# TEC_DRV.net
KiCad netlist of a schematic drawn in Altium Designer
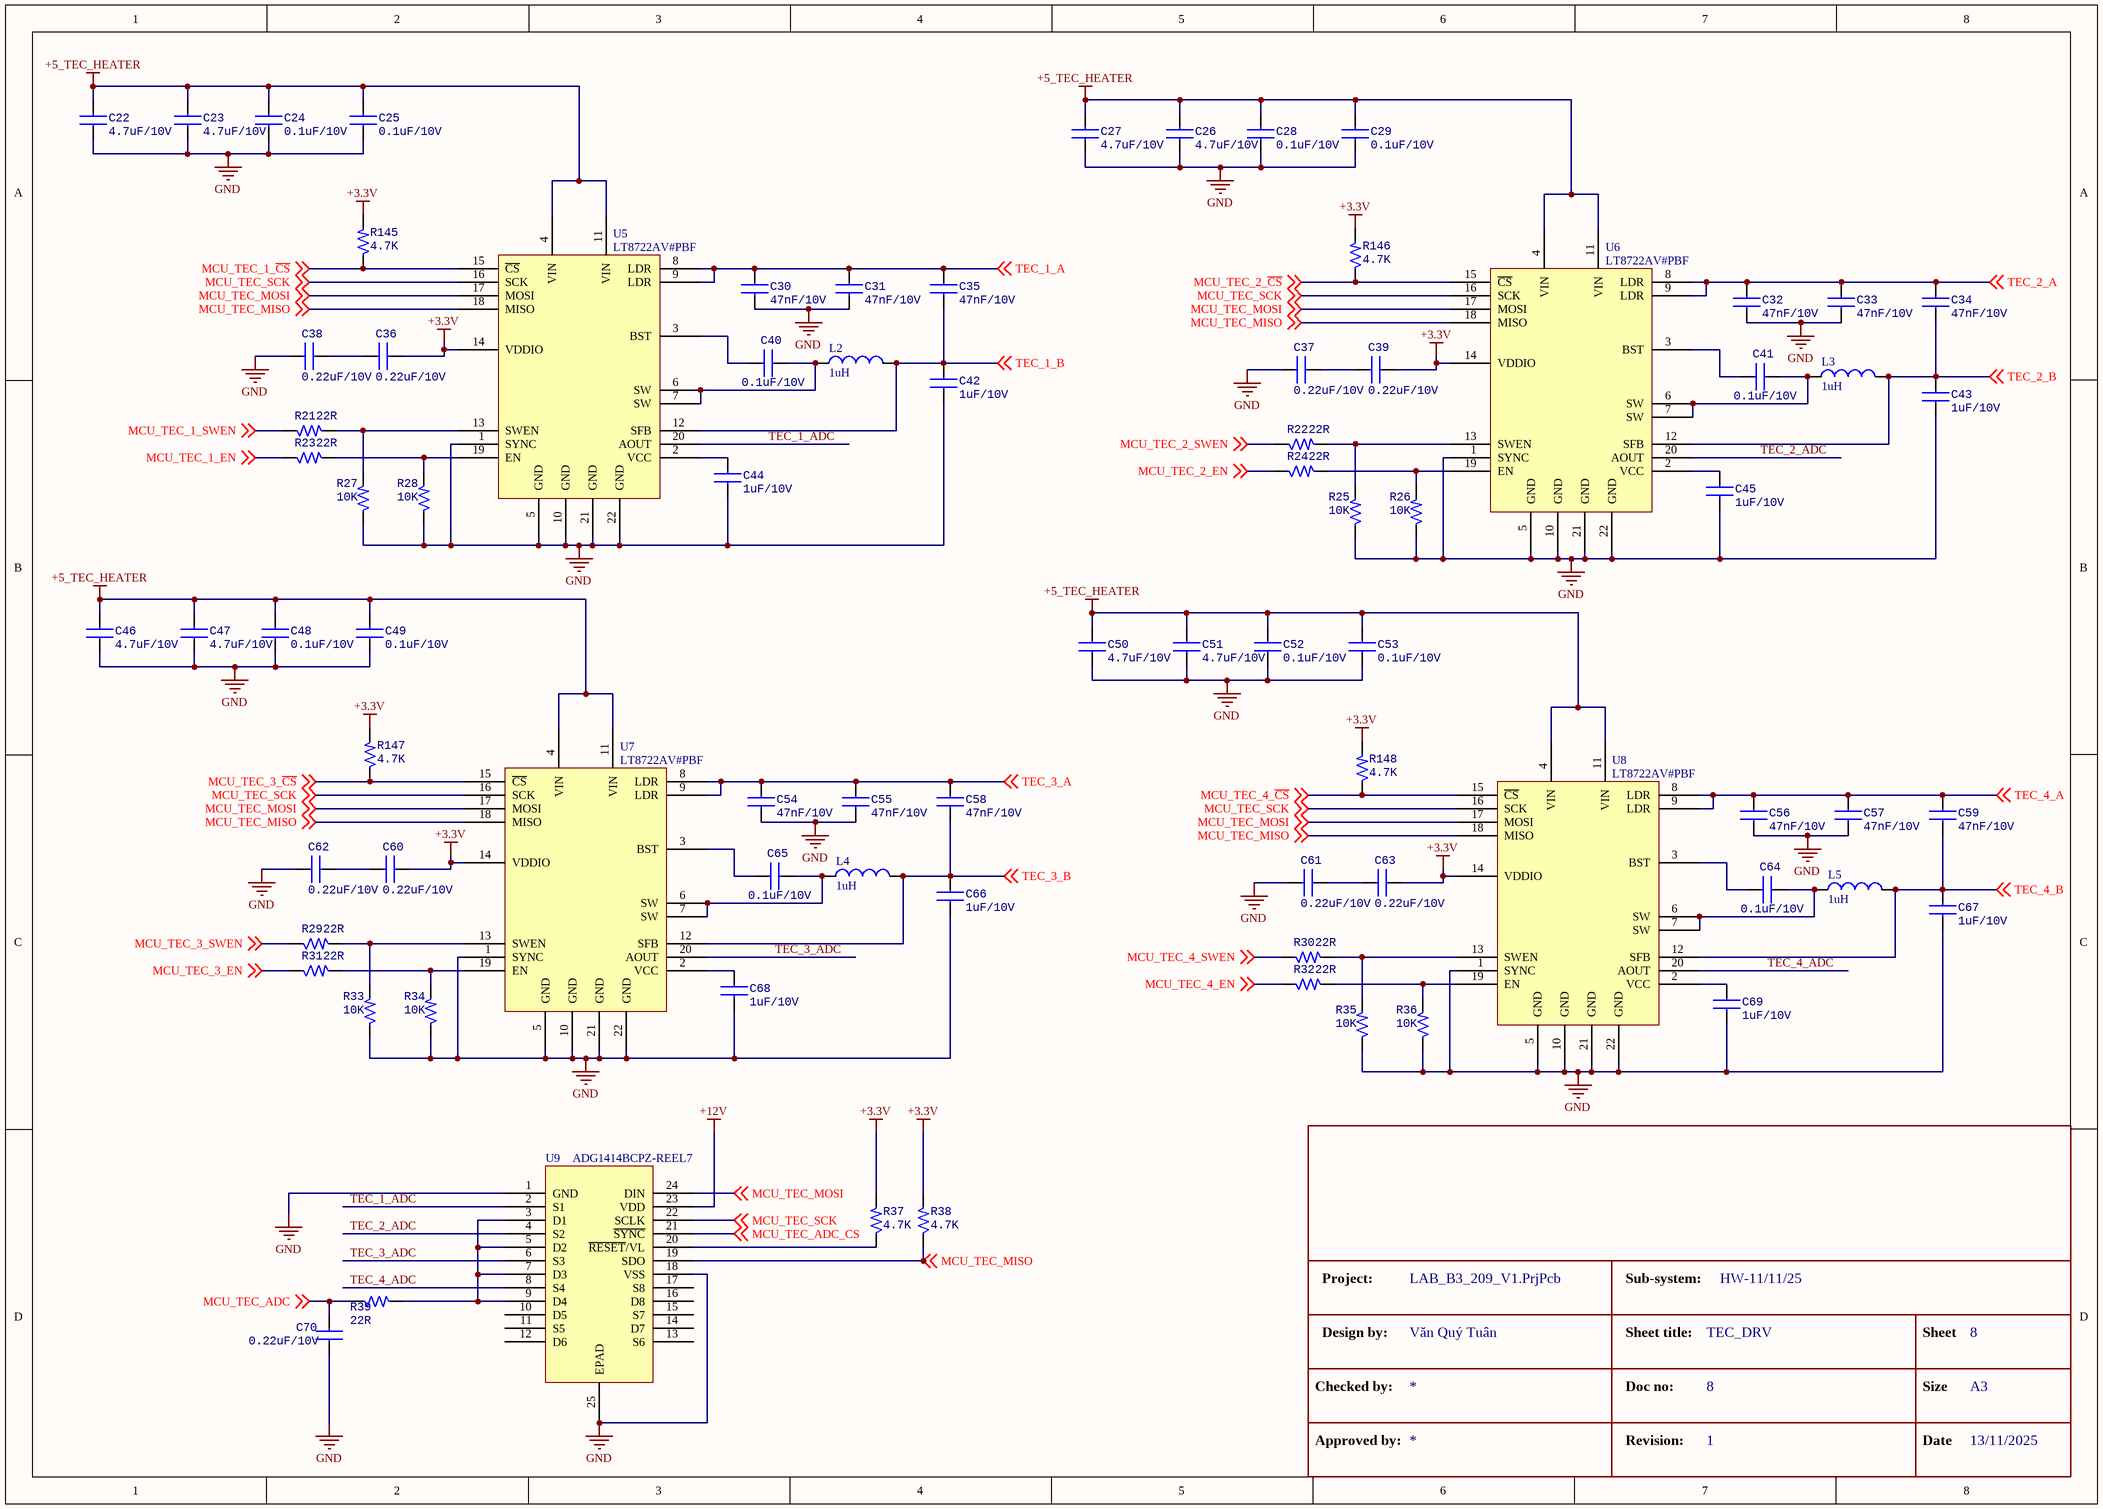
[diagram p0: TEC_DRV.SchDoc]

(export (version "E")
  (design (tool "Eeschema 10.0.6"))
  (components
    (comp (ref "C22") (value "4.7uF/10V") (footprint "CAP-CER-0603") (libsource (lib "ID") (part "CAP-CER")))
    (comp (ref "C23") (value "4.7uF/10V") (footprint "CAP-CER-0603") (libsource (lib "ID") (part "CAP-CER")))
    (comp (ref "C24") (value "0.1uF/10V") (footprint "CAP-CER-0603") (libsource (lib "ID") (part "CAP-CER")))
    (comp (ref "C25") (value "0.1uF/10V") (footprint "CAP-CER-0603") (libsource (lib "ID") (part "CAP-CER")))
    (comp (ref "C26") (value "4.7uF/10V") (footprint "CAP-CER-0603") (libsource (lib "ID") (part "CAP-CER")))
    (comp (ref "C27") (value "4.7uF/10V") (footprint "CAP-CER-0603") (libsource (lib "ID") (part "CAP-CER")))
    (comp (ref "C28") (value "0.1uF/10V") (footprint "CAP-CER-0603") (libsource (lib "ID") (part "CAP-CER")))
    (comp (ref "C29") (value "0.1uF/10V") (footprint "CAP-CER-0603") (libsource (lib "ID") (part "CAP-CER")))
    (comp (ref "C30") (value "47nF/10V") (footprint "CAP-CER-0603") (libsource (lib "ID") (part "CAP-CER")))
    (comp (ref "C31") (value "47nF/10V") (footprint "CAP-CER-0603") (libsource (lib "ID") (part "CAP-CER")))
    (comp (ref "C32") (value "47nF/10V") (footprint "CAP-CER-0603") (libsource (lib "ID") (part "CAP-CER")))
    (comp (ref "C33") (value "47nF/10V") (footprint "CAP-CER-0603") (libsource (lib "ID") (part "CAP-CER")))
    (comp (ref "C34") (value "47nF/10V") (footprint "CAP-CER-0603") (libsource (lib "ID") (part "CAP-CER")))
    (comp (ref "C35") (value "47nF/10V") (footprint "CAP-CER-0603") (libsource (lib "ID") (part "CAP-CER")))
    (comp (ref "C36") (value "0.22uF/10V") (footprint "CAP-CER-0603") (libsource (lib "ID") (part "CAP-CER")))
    (comp (ref "C37") (value "0.22uF/10V") (footprint "CAP-CER-0603") (libsource (lib "ID") (part "CAP-CER")))
    (comp (ref "C38") (value "0.22uF/10V") (footprint "CAP-CER-0603") (libsource (lib "ID") (part "CAP-CER")))
    (comp (ref "C39") (value "0.22uF/10V") (footprint "CAP-CER-0603") (libsource (lib "ID") (part "CAP-CER")))
    (comp (ref "C40") (value "0.1uF/10V") (footprint "CAP-CER-0603") (libsource (lib "ID") (part "CAP-CER")))
    (comp (ref "C41") (value "0.1uF/10V") (footprint "CAP-CER-0603") (libsource (lib "ID") (part "CAP-CER")))
    (comp (ref "C42") (value "1uF/10V") (footprint "CAP-CER-0603") (libsource (lib "ID") (part "CAP-CER")))
    (comp (ref "C43") (value "1uF/10V") (footprint "CAP-CER-0603") (libsource (lib "ID") (part "CAP-CER")))
    (comp (ref "C44") (value "1uF/10V") (footprint "CAP-CER-0603") (libsource (lib "ID") (part "CAP-CER")))
    (comp (ref "C45") (value "1uF/10V") (footprint "CAP-CER-0603") (libsource (lib "ID") (part "CAP-CER")))
    (comp (ref "C46") (value "4.7uF/10V") (footprint "CAP-CER-0603") (libsource (lib "ID") (part "CAP-CER")))
    (comp (ref "C47") (value "4.7uF/10V") (footprint "CAP-CER-0603") (libsource (lib "ID") (part "CAP-CER")))
    (comp (ref "C48") (value "0.1uF/10V") (footprint "CAP-CER-0603") (libsource (lib "ID") (part "CAP-CER")))
    (comp (ref "C49") (value "0.1uF/10V") (footprint "CAP-CER-0603") (libsource (lib "ID") (part "CAP-CER")))
    (comp (ref "C50") (value "4.7uF/10V") (footprint "CAP-CER-0603") (libsource (lib "ID") (part "CAP-CER")))
    (comp (ref "C51") (value "4.7uF/10V") (footprint "CAP-CER-0603") (libsource (lib "ID") (part "CAP-CER")))
    (comp (ref "C52") (value "0.1uF/10V") (footprint "CAP-CER-0603") (libsource (lib "ID") (part "CAP-CER")))
    (comp (ref "C53") (value "0.1uF/10V") (footprint "CAP-CER-0603") (libsource (lib "ID") (part "CAP-CER")))
    (comp (ref "C54") (value "47nF/10V") (footprint "CAP-CER-0603") (libsource (lib "ID") (part "CAP-CER")))
    (comp (ref "C55") (value "47nF/10V") (footprint "CAP-CER-0603") (libsource (lib "ID") (part "CAP-CER")))
    (comp (ref "C56") (value "47nF/10V") (footprint "CAP-CER-0603") (libsource (lib "ID") (part "CAP-CER")))
    (comp (ref "C57") (value "47nF/10V") (footprint "CAP-CER-0603") (libsource (lib "ID") (part "CAP-CER")))
    (comp (ref "C58") (value "47nF/10V") (footprint "CAP-CER-0603") (libsource (lib "ID") (part "CAP-CER")))
    (comp (ref "C59") (value "47nF/10V") (footprint "CAP-CER-0603") (libsource (lib "ID") (part "CAP-CER")))
    (comp (ref "C60") (value "0.22uF/10V") (footprint "CAP-CER-0603") (libsource (lib "ID") (part "CAP-CER")))
    (comp (ref "C61") (value "0.22uF/10V") (footprint "CAP-CER-0603") (libsource (lib "ID") (part "CAP-CER")))
    (comp (ref "C62") (value "0.22uF/10V") (footprint "CAP-CER-0603") (libsource (lib "ID") (part "CAP-CER")))
    (comp (ref "C63") (value "0.22uF/10V") (footprint "CAP-CER-0603") (libsource (lib "ID") (part "CAP-CER")))
    (comp (ref "C64") (value "0.1uF/10V") (footprint "CAP-CER-0603") (libsource (lib "ID") (part "CAP-CER")))
    (comp (ref "C65") (value "0.1uF/10V") (footprint "CAP-CER-0603") (libsource (lib "ID") (part "CAP-CER")))
    (comp (ref "C66") (value "1uF/10V") (footprint "CAP-CER-0603") (libsource (lib "ID") (part "CAP-CER")))
    (comp (ref "C67") (value "1uF/10V") (footprint "CAP-CER-0603") (libsource (lib "ID") (part "CAP-CER")))
    (comp (ref "C68") (value "1uF/10V") (footprint "CAP-CER-0603") (libsource (lib "ID") (part "CAP-CER")))
    (comp (ref "C69") (value "1uF/10V") (footprint "CAP-CER-0603") (libsource (lib "ID") (part "CAP-CER")))
    (comp (ref "C70") (value "0.22uF/10V") (footprint "CAP-CER-0603") (libsource (lib "ID") (part "CAP-CER")))
    (comp (ref "L2")
      (value "1uH")
      (footprint "INDUCTOR-FIXED IND 1UH 4A 38 MOHM SMD")
      (fields (field (name "MP") "LQM18PZ2R2MFHD") (field (name "MF") "Murata"))
      (libsource (lib "ID") (part "INDUCT-SMD"))
    )
    (comp (ref "L3")
      (value "1uH")
      (footprint "INDUCTOR-FIXED IND 1UH 4A 38 MOHM SMD")
      (fields (field (name "MP") "LQM18PZ2R2MFHD") (field (name "MF") "Murata"))
      (libsource (lib "ID") (part "INDUCT-SMD"))
    )
    (comp (ref "L4")
      (value "1uH")
      (footprint "INDUCTOR-FIXED IND 1UH 4A 38 MOHM SMD")
      (fields (field (name "MP") "LQM18PZ2R2MFHD") (field (name "MF") "Murata"))
      (libsource (lib "ID") (part "INDUCT-SMD"))
    )
    (comp (ref "L5")
      (value "1uH")
      (footprint "INDUCTOR-FIXED IND 1UH 4A 38 MOHM SMD")
      (fields (field (name "MP") "LQM18PZ2R2MFHD") (field (name "MF") "Murata"))
      (libsource (lib "ID") (part "INDUCT-SMD"))
    )
    (comp (ref "R21") (value "22R") (footprint "RES-SMD-0603") (libsource (lib "ID") (part "RES-SMD")))
    (comp (ref "R22") (value "22R") (footprint "RES-SMD-0603") (libsource (lib "ID") (part "RES-SMD")))
    (comp (ref "R23") (value "22R") (footprint "RES-SMD-0603") (libsource (lib "ID") (part "RES-SMD")))
    (comp (ref "R24") (value "22R") (footprint "RES-SMD-0603") (libsource (lib "ID") (part "RES-SMD")))
    (comp (ref "R25") (value "10K") (footprint "RES-SMD-0603") (libsource (lib "ID") (part "RES-SMD")))
    (comp (ref "R26") (value "10K") (footprint "RES-SMD-0603") (libsource (lib "ID") (part "RES-SMD")))
    (comp (ref "R27") (value "10K") (footprint "RES-SMD-0603") (libsource (lib "ID") (part "RES-SMD")))
    (comp (ref "R28") (value "10K") (footprint "RES-SMD-0603") (libsource (lib "ID") (part "RES-SMD")))
    (comp (ref "R29") (value "22R") (footprint "RES-SMD-0603") (libsource (lib "ID") (part "RES-SMD")))
    (comp (ref "R30") (value "22R") (footprint "RES-SMD-0603") (libsource (lib "ID") (part "RES-SMD")))
    (comp (ref "R31") (value "22R") (footprint "RES-SMD-0603") (libsource (lib "ID") (part "RES-SMD")))
    (comp (ref "R32") (value "22R") (footprint "RES-SMD-0603") (libsource (lib "ID") (part "RES-SMD")))
    (comp (ref "R33") (value "10K") (footprint "RES-SMD-0603") (libsource (lib "ID") (part "RES-SMD")))
    (comp (ref "R34") (value "10K") (footprint "RES-SMD-0603") (libsource (lib "ID") (part "RES-SMD")))
    (comp (ref "R35") (value "10K") (footprint "RES-SMD-0603") (libsource (lib "ID") (part "RES-SMD")))
    (comp (ref "R36") (value "10K") (footprint "RES-SMD-0603") (libsource (lib "ID") (part "RES-SMD")))
    (comp (ref "R37") (value "4.7K") (footprint "RES-SMD-0603") (libsource (lib "ID") (part "RES-SMD")))
    (comp (ref "R38") (value "4.7K") (footprint "RES-SMD-0603") (libsource (lib "ID") (part "RES-SMD")))
    (comp (ref "R39") (value "22R") (footprint "RES-SMD-0603") (libsource (lib "ID") (part "RES-SMD")))
    (comp (ref "R145") (value "4.7K") (footprint "RES-SMD-0603") (libsource (lib "ID") (part "RES-SMD")))
    (comp (ref "R146") (value "4.7K") (footprint "RES-SMD-0603") (libsource (lib "ID") (part "RES-SMD")))
    (comp (ref "R147") (value "4.7K") (footprint "RES-SMD-0603") (libsource (lib "ID") (part "RES-SMD")))
    (comp (ref "R148") (value "4.7K") (footprint "RES-SMD-0603") (libsource (lib "ID") (part "RES-SMD")))
    (comp (ref "U5")
      (value "LT8722AV#PBF")
      (footprint "LT8722AV#PBF")
      (libsource (lib "LAB_B3_209_V1") (part "LT8722AV#PBF"))
    )
    (comp (ref "U6")
      (value "LT8722AV#PBF")
      (footprint "LT8722AV#PBF")
      (libsource (lib "LAB_B3_209_V1") (part "LT8722AV#PBF"))
    )
    (comp (ref "U7")
      (value "LT8722AV#PBF")
      (footprint "LT8722AV#PBF")
      (libsource (lib "LAB_B3_209_V1") (part "LT8722AV#PBF"))
    )
    (comp (ref "U8")
      (value "LT8722AV#PBF")
      (footprint "LT8722AV#PBF")
      (libsource (lib "LAB_B3_209_V1") (part "LT8722AV#PBF"))
    )
    (comp (ref "U9")
      (value "ADG1414BCPZ-REEL7")
      (footprint "ADG1414BCPZ-REEL7")
      (libsource (lib "LAB_B3_209_V1") (part "ADG1414BCPZ-REEL7"))
    )
  )
  (nets
    (net (code "1") (name "+3.3V") (class "Default")
      (node (ref "C36") (pin "2") (pinfunction "2_2") (pintype "passive"))
      (node (ref "C39") (pin "2") (pinfunction "2_2") (pintype "passive"))
      (node (ref "C60") (pin "2") (pinfunction "2_2") (pintype "passive"))
      (node (ref "C63") (pin "2") (pinfunction "2_2") (pintype "passive"))
      (node (ref "R145") (pin "2") (pinfunction "2_2") (pintype "passive"))
      (node (ref "R146") (pin "2") (pinfunction "2_2") (pintype "passive"))
      (node (ref "R147") (pin "2") (pinfunction "2_2") (pintype "passive"))
      (node (ref "R148") (pin "2") (pinfunction "2_2") (pintype "passive"))
      (node (ref "R37") (pin "2") (pinfunction "2_2") (pintype "passive"))
      (node (ref "R38") (pin "2") (pinfunction "2_2") (pintype "passive"))
      (node (ref "U5") (pin "14") (pinfunction "VDDIO_14") (pintype "passive"))
      (node (ref "U6") (pin "14") (pinfunction "VDDIO_14") (pintype "passive"))
      (node (ref "U7") (pin "14") (pinfunction "VDDIO_14") (pintype "passive"))
      (node (ref "U8") (pin "14") (pinfunction "VDDIO_14") (pintype "passive"))
    )
    (net (code "2") (name "+5_TEC_HEATER") (class "Default")
      (node (ref "C22") (pin "1") (pinfunction "1_1") (pintype "passive"))
      (node (ref "C23") (pin "1") (pinfunction "1_1") (pintype "passive"))
      (node (ref "C24") (pin "1") (pinfunction "1_1") (pintype "passive"))
      (node (ref "C25") (pin "1") (pinfunction "1_1") (pintype "passive"))
      (node (ref "C26") (pin "1") (pinfunction "1_1") (pintype "passive"))
      (node (ref "C27") (pin "1") (pinfunction "1_1") (pintype "passive"))
      (node (ref "C28") (pin "1") (pinfunction "1_1") (pintype "passive"))
      (node (ref "C29") (pin "1") (pinfunction "1_1") (pintype "passive"))
      (node (ref "C46") (pin "1") (pinfunction "1_1") (pintype "passive"))
      (node (ref "C47") (pin "1") (pinfunction "1_1") (pintype "passive"))
      (node (ref "C48") (pin "1") (pinfunction "1_1") (pintype "passive"))
      (node (ref "C49") (pin "1") (pinfunction "1_1") (pintype "passive"))
      (node (ref "C50") (pin "1") (pinfunction "1_1") (pintype "passive"))
      (node (ref "C51") (pin "1") (pinfunction "1_1") (pintype "passive"))
      (node (ref "C52") (pin "1") (pinfunction "1_1") (pintype "passive"))
      (node (ref "C53") (pin "1") (pinfunction "1_1") (pintype "passive"))
      (node (ref "U5") (pin "11") (pinfunction "VIN_11") (pintype "passive"))
      (node (ref "U5") (pin "4") (pinfunction "VIN_4") (pintype "passive"))
      (node (ref "U6") (pin "11") (pinfunction "VIN_11") (pintype "passive"))
      (node (ref "U6") (pin "4") (pinfunction "VIN_4") (pintype "passive"))
      (node (ref "U7") (pin "11") (pinfunction "VIN_11") (pintype "passive"))
      (node (ref "U7") (pin "4") (pinfunction "VIN_4") (pintype "passive"))
      (node (ref "U8") (pin "11") (pinfunction "VIN_11") (pintype "passive"))
      (node (ref "U8") (pin "4") (pinfunction "VIN_4") (pintype "passive"))
    )
    (net (code "3") (name "+12V") (class "Default")
      (node (ref "U9") (pin "23") (pinfunction "VDD_23") (pintype "passive"))
    )
    (net (code "4") (name "/TEC_1_ADC") (class "Default")
      (node (ref "U5") (pin "20") (pinfunction "AOUT_20") (pintype "passive"))
      (node (ref "U9") (pin "2") (pinfunction "S1_2") (pintype "passive"))
    )
    (net (code "5") (name "/TEC_2_ADC") (class "Default")
      (node (ref "U6") (pin "20") (pinfunction "AOUT_20") (pintype "passive"))
      (node (ref "U9") (pin "4") (pinfunction "S2_4") (pintype "passive"))
    )
    (net (code "6") (name "/TEC_3_ADC") (class "Default")
      (node (ref "U7") (pin "20") (pinfunction "AOUT_20") (pintype "passive"))
      (node (ref "U9") (pin "6") (pinfunction "S3_6") (pintype "passive"))
    )
    (net (code "7") (name "/TEC_4_ADC") (class "Default")
      (node (ref "U8") (pin "20") (pinfunction "AOUT_20") (pintype "passive"))
      (node (ref "U9") (pin "8") (pinfunction "S4_8") (pintype "passive"))
    )
    (net (code "8") (name "GND") (class "Default")
      (node (ref "C22") (pin "2") (pinfunction "2_2") (pintype "passive"))
      (node (ref "C23") (pin "2") (pinfunction "2_2") (pintype "passive"))
      (node (ref "C24") (pin "2") (pinfunction "2_2") (pintype "passive"))
      (node (ref "C25") (pin "2") (pinfunction "2_2") (pintype "passive"))
      (node (ref "C26") (pin "2") (pinfunction "2_2") (pintype "passive"))
      (node (ref "C27") (pin "2") (pinfunction "2_2") (pintype "passive"))
      (node (ref "C28") (pin "2") (pinfunction "2_2") (pintype "passive"))
      (node (ref "C29") (pin "2") (pinfunction "2_2") (pintype "passive"))
      (node (ref "C30") (pin "1") (pinfunction "1_1") (pintype "passive"))
      (node (ref "C31") (pin "1") (pinfunction "1_1") (pintype "passive"))
      (node (ref "C32") (pin "1") (pinfunction "1_1") (pintype "passive"))
      (node (ref "C33") (pin "1") (pinfunction "1_1") (pintype "passive"))
      (node (ref "C37") (pin "2") (pinfunction "2_2") (pintype "passive"))
      (node (ref "C38") (pin "2") (pinfunction "2_2") (pintype "passive"))
      (node (ref "C42") (pin "1") (pinfunction "1_1") (pintype "passive"))
      (node (ref "C43") (pin "1") (pinfunction "1_1") (pintype "passive"))
      (node (ref "C44") (pin "1") (pinfunction "1_1") (pintype "passive"))
      (node (ref "C45") (pin "1") (pinfunction "1_1") (pintype "passive"))
      (node (ref "C46") (pin "2") (pinfunction "2_2") (pintype "passive"))
      (node (ref "C47") (pin "2") (pinfunction "2_2") (pintype "passive"))
      (node (ref "C48") (pin "2") (pinfunction "2_2") (pintype "passive"))
      (node (ref "C49") (pin "2") (pinfunction "2_2") (pintype "passive"))
      (node (ref "C50") (pin "2") (pinfunction "2_2") (pintype "passive"))
      (node (ref "C51") (pin "2") (pinfunction "2_2") (pintype "passive"))
      (node (ref "C52") (pin "2") (pinfunction "2_2") (pintype "passive"))
      (node (ref "C53") (pin "2") (pinfunction "2_2") (pintype "passive"))
      (node (ref "C54") (pin "1") (pinfunction "1_1") (pintype "passive"))
      (node (ref "C55") (pin "1") (pinfunction "1_1") (pintype "passive"))
      (node (ref "C56") (pin "1") (pinfunction "1_1") (pintype "passive"))
      (node (ref "C57") (pin "1") (pinfunction "1_1") (pintype "passive"))
      (node (ref "C61") (pin "2") (pinfunction "2_2") (pintype "passive"))
      (node (ref "C62") (pin "2") (pinfunction "2_2") (pintype "passive"))
      (node (ref "C66") (pin "1") (pinfunction "1_1") (pintype "passive"))
      (node (ref "C67") (pin "1") (pinfunction "1_1") (pintype "passive"))
      (node (ref "C68") (pin "1") (pinfunction "1_1") (pintype "passive"))
      (node (ref "C69") (pin "1") (pinfunction "1_1") (pintype "passive"))
      (node (ref "C70") (pin "2") (pinfunction "2_2") (pintype "passive"))
      (node (ref "R25") (pin "1") (pinfunction "1_1") (pintype "passive"))
      (node (ref "R26") (pin "1") (pinfunction "1_1") (pintype "passive"))
      (node (ref "R27") (pin "1") (pinfunction "1_1") (pintype "passive"))
      (node (ref "R28") (pin "1") (pinfunction "1_1") (pintype "passive"))
      (node (ref "R33") (pin "1") (pinfunction "1_1") (pintype "passive"))
      (node (ref "R34") (pin "1") (pinfunction "1_1") (pintype "passive"))
      (node (ref "R35") (pin "1") (pinfunction "1_1") (pintype "passive"))
      (node (ref "R36") (pin "1") (pinfunction "1_1") (pintype "passive"))
      (node (ref "U5") (pin "1") (pinfunction "SYNC_1") (pintype "passive"))
      (node (ref "U5") (pin "10") (pinfunction "GND_10") (pintype "passive"))
      (node (ref "U5") (pin "21") (pinfunction "GND_21") (pintype "passive"))
      (node (ref "U5") (pin "22") (pinfunction "GND_22") (pintype "passive"))
      (node (ref "U5") (pin "5") (pinfunction "GND_5") (pintype "passive"))
      (node (ref "U6") (pin "1") (pinfunction "SYNC_1") (pintype "passive"))
      (node (ref "U6") (pin "10") (pinfunction "GND_10") (pintype "passive"))
      (node (ref "U6") (pin "21") (pinfunction "GND_21") (pintype "passive"))
      (node (ref "U6") (pin "22") (pinfunction "GND_22") (pintype "passive"))
      (node (ref "U6") (pin "5") (pinfunction "GND_5") (pintype "passive"))
      (node (ref "U7") (pin "1") (pinfunction "SYNC_1") (pintype "passive"))
      (node (ref "U7") (pin "10") (pinfunction "GND_10") (pintype "passive"))
      (node (ref "U7") (pin "21") (pinfunction "GND_21") (pintype "passive"))
      (node (ref "U7") (pin "22") (pinfunction "GND_22") (pintype "passive"))
      (node (ref "U7") (pin "5") (pinfunction "GND_5") (pintype "passive"))
      (node (ref "U8") (pin "1") (pinfunction "SYNC_1") (pintype "passive"))
      (node (ref "U8") (pin "10") (pinfunction "GND_10") (pintype "passive"))
      (node (ref "U8") (pin "21") (pinfunction "GND_21") (pintype "passive"))
      (node (ref "U8") (pin "22") (pinfunction "GND_22") (pintype "passive"))
      (node (ref "U8") (pin "5") (pinfunction "GND_5") (pintype "passive"))
      (node (ref "U9") (pin "1") (pinfunction "GND_1") (pintype "passive"))
      (node (ref "U9") (pin "18") (pinfunction "VSS_18") (pintype "passive"))
      (node (ref "U9") (pin "25") (pinfunction "EPAD_25") (pintype "passive"))
    )
    (net (code "9") (name "MCU_TEC_1_EN") (class "Default")
      (node (ref "R23") (pin "1") (pinfunction "1_1") (pintype "passive"))
    )
    (net (code "10") (name "MCU_TEC_1_SWEN") (class "Default")
      (node (ref "R21") (pin "1") (pinfunction "1_1") (pintype "passive"))
    )
    (net (code "11") (name "MCU_TEC_1_~{CS}") (class "Default")
      (node (ref "R145") (pin "1") (pinfunction "1_1") (pintype "passive"))
      (node (ref "U5") (pin "15") (pinfunction "~{CS}_15") (pintype "passive"))
    )
    (net (code "12") (name "MCU_TEC_2_EN") (class "Default")
      (node (ref "R24") (pin "1") (pinfunction "1_1") (pintype "passive"))
    )
    (net (code "13") (name "MCU_TEC_2_SWEN") (class "Default")
      (node (ref "R22") (pin "1") (pinfunction "1_1") (pintype "passive"))
    )
    (net (code "14") (name "MCU_TEC_2_~{CS}") (class "Default")
      (node (ref "R146") (pin "1") (pinfunction "1_1") (pintype "passive"))
      (node (ref "U6") (pin "15") (pinfunction "~{CS}_15") (pintype "passive"))
    )
    (net (code "15") (name "MCU_TEC_3_EN") (class "Default")
      (node (ref "R31") (pin "1") (pinfunction "1_1") (pintype "passive"))
    )
    (net (code "16") (name "MCU_TEC_3_SWEN") (class "Default")
      (node (ref "R29") (pin "1") (pinfunction "1_1") (pintype "passive"))
    )
    (net (code "17") (name "MCU_TEC_3_~{CS}") (class "Default")
      (node (ref "R147") (pin "1") (pinfunction "1_1") (pintype "passive"))
      (node (ref "U7") (pin "15") (pinfunction "~{CS}_15") (pintype "passive"))
    )
    (net (code "18") (name "MCU_TEC_4_EN") (class "Default")
      (node (ref "R32") (pin "1") (pinfunction "1_1") (pintype "passive"))
    )
    (net (code "19") (name "MCU_TEC_4_SWEN") (class "Default")
      (node (ref "R30") (pin "1") (pinfunction "1_1") (pintype "passive"))
    )
    (net (code "20") (name "MCU_TEC_4_~{CS}") (class "Default")
      (node (ref "R148") (pin "1") (pinfunction "1_1") (pintype "passive"))
      (node (ref "U8") (pin "15") (pinfunction "~{CS}_15") (pintype "passive"))
    )
    (net (code "21") (name "MCU_TEC_ADC") (class "Default")
      (node (ref "C70") (pin "1") (pinfunction "1_1") (pintype "passive"))
      (node (ref "R39") (pin "1") (pinfunction "1_1") (pintype "passive"))
    )
    (net (code "22") (name "MCU_TEC_ADC_CS") (class "Default")
      (node (ref "U9") (pin "21") (pinfunction "~{SYNC}_21") (pintype "passive"))
    )
    (net (code "23") (name "MCU_TEC_MISO") (class "Default")
      (node (ref "R38") (pin "1") (pinfunction "1_1") (pintype "passive"))
      (node (ref "U5") (pin "18") (pinfunction "MISO_18") (pintype "passive"))
      (node (ref "U6") (pin "18") (pinfunction "MISO_18") (pintype "passive"))
      (node (ref "U7") (pin "18") (pinfunction "MISO_18") (pintype "passive"))
      (node (ref "U8") (pin "18") (pinfunction "MISO_18") (pintype "passive"))
      (node (ref "U9") (pin "19") (pinfunction "SDO_19") (pintype "passive"))
    )
    (net (code "24") (name "MCU_TEC_MOSI") (class "Default")
      (node (ref "U5") (pin "17") (pinfunction "MOSI_17") (pintype "passive"))
      (node (ref "U6") (pin "17") (pinfunction "MOSI_17") (pintype "passive"))
      (node (ref "U7") (pin "17") (pinfunction "MOSI_17") (pintype "passive"))
      (node (ref "U8") (pin "17") (pinfunction "MOSI_17") (pintype "passive"))
      (node (ref "U9") (pin "24") (pinfunction "DIN_24") (pintype "passive"))
    )
    (net (code "25") (name "MCU_TEC_SCK") (class "Default")
      (node (ref "U5") (pin "16") (pinfunction "SCK_16") (pintype "passive"))
      (node (ref "U6") (pin "16") (pinfunction "SCK_16") (pintype "passive"))
      (node (ref "U7") (pin "16") (pinfunction "SCK_16") (pintype "passive"))
      (node (ref "U8") (pin "16") (pinfunction "SCK_16") (pintype "passive"))
      (node (ref "U9") (pin "22") (pinfunction "SCLK_22") (pintype "passive"))
    )
    (net (code "26") (name "Net-(C36-Pad1)") (class "Default")
      (node (ref "C36") (pin "1") (pinfunction "1_1") (pintype "passive"))
      (node (ref "C38") (pin "1") (pinfunction "1_1") (pintype "passive"))
    )
    (net (code "27") (name "Net-(C37-Pad1)") (class "Default")
      (node (ref "C37") (pin "1") (pinfunction "1_1") (pintype "passive"))
      (node (ref "C39") (pin "1") (pinfunction "1_1") (pintype "passive"))
    )
    (net (code "28") (name "Net-(C40-Pad1)") (class "Default")
      (node (ref "C40") (pin "1") (pinfunction "1_1") (pintype "passive"))
      (node (ref "L2") (pin "1") (pinfunction "1_1") (pintype "passive"))
      (node (ref "U5") (pin "6") (pinfunction "SW_6") (pintype "passive"))
      (node (ref "U5") (pin "7") (pinfunction "SW_7") (pintype "passive"))
    )
    (net (code "29") (name "Net-(C41-Pad1)") (class "Default")
      (node (ref "C41") (pin "1") (pinfunction "1_1") (pintype "passive"))
      (node (ref "L3") (pin "1") (pinfunction "1_1") (pintype "passive"))
      (node (ref "U6") (pin "6") (pinfunction "SW_6") (pintype "passive"))
      (node (ref "U6") (pin "7") (pinfunction "SW_7") (pintype "passive"))
    )
    (net (code "30") (name "Net-(C60-Pad1)") (class "Default")
      (node (ref "C60") (pin "1") (pinfunction "1_1") (pintype "passive"))
      (node (ref "C62") (pin "1") (pinfunction "1_1") (pintype "passive"))
    )
    (net (code "31") (name "Net-(C61-Pad1)") (class "Default")
      (node (ref "C61") (pin "1") (pinfunction "1_1") (pintype "passive"))
      (node (ref "C63") (pin "1") (pinfunction "1_1") (pintype "passive"))
    )
    (net (code "32") (name "Net-(C64-Pad1)") (class "Default")
      (node (ref "C64") (pin "1") (pinfunction "1_1") (pintype "passive"))
      (node (ref "L5") (pin "1") (pinfunction "1_1") (pintype "passive"))
      (node (ref "U8") (pin "6") (pinfunction "SW_6") (pintype "passive"))
      (node (ref "U8") (pin "7") (pinfunction "SW_7") (pintype "passive"))
    )
    (net (code "33") (name "Net-(C65-Pad1)") (class "Default")
      (node (ref "C65") (pin "1") (pinfunction "1_1") (pintype "passive"))
      (node (ref "L4") (pin "1") (pinfunction "1_1") (pintype "passive"))
      (node (ref "U7") (pin "6") (pinfunction "SW_6") (pintype "passive"))
      (node (ref "U7") (pin "7") (pinfunction "SW_7") (pintype "passive"))
    )
    (net (code "34") (name "Net-(U5-BST)") (class "Default")
      (node (ref "C40") (pin "2") (pinfunction "2_2") (pintype "passive"))
      (node (ref "U5") (pin "3") (pinfunction "BST_3") (pintype "passive"))
    )
    (net (code "35") (name "Net-(U5-EN)") (class "Default")
      (node (ref "R23") (pin "2") (pinfunction "2_2") (pintype "passive"))
      (node (ref "R28") (pin "2") (pinfunction "2_2") (pintype "passive"))
      (node (ref "U5") (pin "19") (pinfunction "EN_19") (pintype "passive"))
    )
    (net (code "36") (name "Net-(U5-SWEN)") (class "Default")
      (node (ref "R21") (pin "2") (pinfunction "2_2") (pintype "passive"))
      (node (ref "R27") (pin "2") (pinfunction "2_2") (pintype "passive"))
      (node (ref "U5") (pin "13") (pinfunction "SWEN_13") (pintype "passive"))
    )
    (net (code "37") (name "Net-(U5-VCC)") (class "Default")
      (node (ref "C44") (pin "2") (pinfunction "2_2") (pintype "passive"))
      (node (ref "U5") (pin "2") (pinfunction "VCC_2") (pintype "passive"))
    )
    (net (code "38") (name "Net-(U6-BST)") (class "Default")
      (node (ref "C41") (pin "2") (pinfunction "2_2") (pintype "passive"))
      (node (ref "U6") (pin "3") (pinfunction "BST_3") (pintype "passive"))
    )
    (net (code "39") (name "Net-(U6-EN)") (class "Default")
      (node (ref "R24") (pin "2") (pinfunction "2_2") (pintype "passive"))
      (node (ref "R26") (pin "2") (pinfunction "2_2") (pintype "passive"))
      (node (ref "U6") (pin "19") (pinfunction "EN_19") (pintype "passive"))
    )
    (net (code "40") (name "Net-(U6-SWEN)") (class "Default")
      (node (ref "R22") (pin "2") (pinfunction "2_2") (pintype "passive"))
      (node (ref "R25") (pin "2") (pinfunction "2_2") (pintype "passive"))
      (node (ref "U6") (pin "13") (pinfunction "SWEN_13") (pintype "passive"))
    )
    (net (code "41") (name "Net-(U6-VCC)") (class "Default")
      (node (ref "C45") (pin "2") (pinfunction "2_2") (pintype "passive"))
      (node (ref "U6") (pin "2") (pinfunction "VCC_2") (pintype "passive"))
    )
    (net (code "42") (name "Net-(U7-BST)") (class "Default")
      (node (ref "C65") (pin "2") (pinfunction "2_2") (pintype "passive"))
      (node (ref "U7") (pin "3") (pinfunction "BST_3") (pintype "passive"))
    )
    (net (code "43") (name "Net-(U7-EN)") (class "Default")
      (node (ref "R31") (pin "2") (pinfunction "2_2") (pintype "passive"))
      (node (ref "R34") (pin "2") (pinfunction "2_2") (pintype "passive"))
      (node (ref "U7") (pin "19") (pinfunction "EN_19") (pintype "passive"))
    )
    (net (code "44") (name "Net-(U7-SWEN)") (class "Default")
      (node (ref "R29") (pin "2") (pinfunction "2_2") (pintype "passive"))
      (node (ref "R33") (pin "2") (pinfunction "2_2") (pintype "passive"))
      (node (ref "U7") (pin "13") (pinfunction "SWEN_13") (pintype "passive"))
    )
    (net (code "45") (name "Net-(U7-VCC)") (class "Default")
      (node (ref "C68") (pin "2") (pinfunction "2_2") (pintype "passive"))
      (node (ref "U7") (pin "2") (pinfunction "VCC_2") (pintype "passive"))
    )
    (net (code "46") (name "Net-(U8-BST)") (class "Default")
      (node (ref "C64") (pin "2") (pinfunction "2_2") (pintype "passive"))
      (node (ref "U8") (pin "3") (pinfunction "BST_3") (pintype "passive"))
    )
    (net (code "47") (name "Net-(U8-EN)") (class "Default")
      (node (ref "R32") (pin "2") (pinfunction "2_2") (pintype "passive"))
      (node (ref "R36") (pin "2") (pinfunction "2_2") (pintype "passive"))
      (node (ref "U8") (pin "19") (pinfunction "EN_19") (pintype "passive"))
    )
    (net (code "48") (name "Net-(U8-SWEN)") (class "Default")
      (node (ref "R30") (pin "2") (pinfunction "2_2") (pintype "passive"))
      (node (ref "R35") (pin "2") (pinfunction "2_2") (pintype "passive"))
      (node (ref "U8") (pin "13") (pinfunction "SWEN_13") (pintype "passive"))
    )
    (net (code "49") (name "Net-(U8-VCC)") (class "Default")
      (node (ref "C69") (pin "2") (pinfunction "2_2") (pintype "passive"))
      (node (ref "U8") (pin "2") (pinfunction "VCC_2") (pintype "passive"))
    )
    (net (code "50") (name "Net-(U9-D1)") (class "Default")
      (node (ref "R39") (pin "2") (pinfunction "2_2") (pintype "passive"))
      (node (ref "U9") (pin "3") (pinfunction "D1_3") (pintype "passive"))
      (node (ref "U9") (pin "5") (pinfunction "D2_5") (pintype "passive"))
      (node (ref "U9") (pin "7") (pinfunction "D3_7") (pintype "passive"))
      (node (ref "U9") (pin "9") (pinfunction "D4_9") (pintype "passive"))
    )
    (net (code "51") (name "Net-(U9-~{RESET}{slash}VL)") (class "Default")
      (node (ref "R37") (pin "1") (pinfunction "1_1") (pintype "passive"))
      (node (ref "U9") (pin "20") (pinfunction "~{RESET}/VL_20") (pintype "passive"))
    )
    (net (code "52") (name "TEC_1_A") (class "Default")
      (node (ref "C30") (pin "2") (pinfunction "2_2") (pintype "passive"))
      (node (ref "C31") (pin "2") (pinfunction "2_2") (pintype "passive"))
      (node (ref "C35") (pin "2") (pinfunction "2_2") (pintype "passive"))
      (node (ref "U5") (pin "8") (pinfunction "LDR_8") (pintype "passive"))
      (node (ref "U5") (pin "9") (pinfunction "LDR_9") (pintype "passive"))
    )
    (net (code "53") (name "TEC_1_B") (class "Default")
      (node (ref "C35") (pin "1") (pinfunction "1_1") (pintype "passive"))
      (node (ref "C42") (pin "2") (pinfunction "2_2") (pintype "passive"))
      (node (ref "L2") (pin "2") (pinfunction "2_2") (pintype "passive"))
      (node (ref "U5") (pin "12") (pinfunction "SFB_12") (pintype "passive"))
    )
    (net (code "54") (name "TEC_2_A") (class "Default")
      (node (ref "C32") (pin "2") (pinfunction "2_2") (pintype "passive"))
      (node (ref "C33") (pin "2") (pinfunction "2_2") (pintype "passive"))
      (node (ref "C34") (pin "2") (pinfunction "2_2") (pintype "passive"))
      (node (ref "U6") (pin "8") (pinfunction "LDR_8") (pintype "passive"))
      (node (ref "U6") (pin "9") (pinfunction "LDR_9") (pintype "passive"))
    )
    (net (code "55") (name "TEC_2_B") (class "Default")
      (node (ref "C34") (pin "1") (pinfunction "1_1") (pintype "passive"))
      (node (ref "C43") (pin "2") (pinfunction "2_2") (pintype "passive"))
      (node (ref "L3") (pin "2") (pinfunction "2_2") (pintype "passive"))
      (node (ref "U6") (pin "12") (pinfunction "SFB_12") (pintype "passive"))
    )
    (net (code "56") (name "TEC_3_A") (class "Default")
      (node (ref "C54") (pin "2") (pinfunction "2_2") (pintype "passive"))
      (node (ref "C55") (pin "2") (pinfunction "2_2") (pintype "passive"))
      (node (ref "C58") (pin "2") (pinfunction "2_2") (pintype "passive"))
      (node (ref "U7") (pin "8") (pinfunction "LDR_8") (pintype "passive"))
      (node (ref "U7") (pin "9") (pinfunction "LDR_9") (pintype "passive"))
    )
    (net (code "57") (name "TEC_3_B") (class "Default")
      (node (ref "C58") (pin "1") (pinfunction "1_1") (pintype "passive"))
      (node (ref "C66") (pin "2") (pinfunction "2_2") (pintype "passive"))
      (node (ref "L4") (pin "2") (pinfunction "2_2") (pintype "passive"))
      (node (ref "U7") (pin "12") (pinfunction "SFB_12") (pintype "passive"))
    )
    (net (code "58") (name "TEC_4_A") (class "Default")
      (node (ref "C56") (pin "2") (pinfunction "2_2") (pintype "passive"))
      (node (ref "C57") (pin "2") (pinfunction "2_2") (pintype "passive"))
      (node (ref "C59") (pin "2") (pinfunction "2_2") (pintype "passive"))
      (node (ref "U8") (pin "8") (pinfunction "LDR_8") (pintype "passive"))
      (node (ref "U8") (pin "9") (pinfunction "LDR_9") (pintype "passive"))
    )
    (net (code "59") (name "TEC_4_B") (class "Default")
      (node (ref "C59") (pin "1") (pinfunction "1_1") (pintype "passive"))
      (node (ref "C67") (pin "2") (pinfunction "2_2") (pintype "passive"))
      (node (ref "L5") (pin "2") (pinfunction "2_2") (pintype "passive"))
      (node (ref "U8") (pin "12") (pinfunction "SFB_12") (pintype "passive"))
    )
    (net (code "60") (name "unconnected-(U9-D5-Pad10)") (class "Default")
      (node (ref "U9") (pin "10") (pinfunction "D5_10") (pintype "passive"))
    )
    (net (code "61") (name "unconnected-(U9-D6-Pad12)") (class "Default")
      (node (ref "U9") (pin "12") (pinfunction "D6_12") (pintype "passive"))
    )
    (net (code "62") (name "unconnected-(U9-D7-Pad14)") (class "Default")
      (node (ref "U9") (pin "14") (pinfunction "D7_14") (pintype "passive"))
    )
    (net (code "63") (name "unconnected-(U9-D8-Pad16)") (class "Default")
      (node (ref "U9") (pin "16") (pinfunction "D8_16") (pintype "passive"))
    )
    (net (code "64") (name "unconnected-(U9-S5-Pad11)") (class "Default")
      (node (ref "U9") (pin "11") (pinfunction "S5_11") (pintype "passive"))
    )
    (net (code "65") (name "unconnected-(U9-S6-Pad13)") (class "Default")
      (node (ref "U9") (pin "13") (pinfunction "S6_13") (pintype "passive"))
    )
    (net (code "66") (name "unconnected-(U9-S7-Pad15)") (class "Default")
      (node (ref "U9") (pin "15") (pinfunction "S7_15") (pintype "passive"))
    )
    (net (code "67") (name "unconnected-(U9-S8-Pad17)") (class "Default")
      (node (ref "U9") (pin "17") (pinfunction "S8_17") (pintype "passive"))
    )
  )
)
